# seg7_minishield.net
KiCad netlist of a schematic drawn in EAGLE
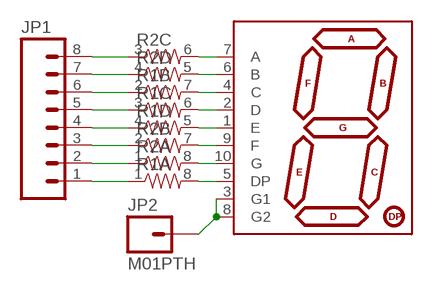
[diagram p0: schematic, sheet 1]

(export (version "E")
  (design (tool "Eeschema 10.0.6"))
  (components
    (comp (ref "JP1")
      (value "M081X08")
      (footprint "eagle-import:1X08")
      (libsource (lib "eagle-import") (part "M081X08"))
    )
    (comp (ref "JP2")
      (value "M01PTH")
      (footprint "eagle-import:1X01")
      (libsource (lib "eagle-import") (part "M01PTH"))
    )
    (comp (ref "R1")
      (value "RESISTOR-ARRAY0603-ARV")
      (footprint "eagle-import:0603-ARV")
      (libsource (lib "eagle-import") (part "RESISTOR-ARRAY0603-ARV"))
    )
    (comp (ref "R2")
      (value "RESISTOR-ARRAY0603-ARV")
      (footprint "eagle-import:0603-ARV")
      (libsource (lib "eagle-import") (part "RESISTOR-ARRAY0603-ARV"))
    )
    (comp (ref "U$1")
      (value "7-SEGMENT-DISPLAYPTH")
      (footprint "eagle-import:7-SEGMENT-DISPLAY")
      (libsource (lib "eagle-import") (part "7-SEGMENT-DISPLAYPTH"))
    )
  )
  (nets
    (net (code "1") (name "Net-(JP1-Pad1)") (class "Default")
      (node (ref "JP1") (pin "1") (pinfunction "1_1") (pintype "passive"))
      (node (ref "R1") (pin "1") (pinfunction "1_1") (pintype "passive"))
    )
    (net (code "2") (name "Net-(JP1-Pad2)") (class "Default")
      (node (ref "JP1") (pin "2") (pinfunction "2_2") (pintype "passive"))
      (node (ref "R2") (pin "1") (pinfunction "1_1") (pintype "passive"))
    )
    (net (code "3") (name "Net-(R1A-2)") (class "Default")
      (node (ref "R1") (pin "8") (pinfunction "2_8") (pintype "passive"))
      (node (ref "U$1") (pin "5") (pinfunction "DP_5") (pintype "bidirectional"))
    )
    (net (code "4") (name "Net-(R1B-1)") (class "Default")
      (node (ref "JP1") (pin "6") (pinfunction "6_6") (pintype "passive"))
      (node (ref "R1") (pin "2") (pinfunction "1_2") (pintype "passive"))
    )
    (net (code "5") (name "Net-(R1B-2)") (class "Default")
      (node (ref "R1") (pin "7") (pinfunction "2_7") (pintype "passive"))
      (node (ref "U$1") (pin "4") (pinfunction "C_4") (pintype "bidirectional"))
    )
    (net (code "6") (name "Net-(R1C-1)") (class "Default")
      (node (ref "JP1") (pin "5") (pinfunction "5_5") (pintype "passive"))
      (node (ref "R1") (pin "3") (pinfunction "1_3") (pintype "passive"))
    )
    (net (code "7") (name "Net-(R1C-2)") (class "Default")
      (node (ref "R1") (pin "6") (pinfunction "2_6") (pintype "passive"))
      (node (ref "U$1") (pin "2") (pinfunction "D_2") (pintype "bidirectional"))
    )
    (net (code "8") (name "Net-(R1D-1)") (class "Default")
      (node (ref "JP1") (pin "4") (pinfunction "4_4") (pintype "passive"))
      (node (ref "R1") (pin "4") (pinfunction "1_4") (pintype "passive"))
    )
    (net (code "9") (name "Net-(R1D-2)") (class "Default")
      (node (ref "R1") (pin "5") (pinfunction "2_5") (pintype "passive"))
      (node (ref "U$1") (pin "1") (pinfunction "E_1") (pintype "bidirectional"))
    )
    (net (code "10") (name "Net-(R2A-2)") (class "Default")
      (node (ref "R2") (pin "8") (pinfunction "2_8") (pintype "passive"))
      (node (ref "U$1") (pin "10") (pinfunction "G_10") (pintype "bidirectional"))
    )
    (net (code "11") (name "Net-(R2B-1)") (class "Default")
      (node (ref "JP1") (pin "3") (pinfunction "3_3") (pintype "passive"))
      (node (ref "R2") (pin "2") (pinfunction "1_2") (pintype "passive"))
    )
    (net (code "12") (name "Net-(R2B-2)") (class "Default")
      (node (ref "R2") (pin "7") (pinfunction "2_7") (pintype "passive"))
      (node (ref "U$1") (pin "9") (pinfunction "F_9") (pintype "bidirectional"))
    )
    (net (code "13") (name "Net-(R2C-1)") (class "Default")
      (node (ref "JP1") (pin "8") (pinfunction "8_8") (pintype "passive"))
      (node (ref "R2") (pin "3") (pinfunction "1_3") (pintype "passive"))
    )
    (net (code "14") (name "Net-(R2C-2)") (class "Default")
      (node (ref "R2") (pin "6") (pinfunction "2_6") (pintype "passive"))
      (node (ref "U$1") (pin "7") (pinfunction "A_7") (pintype "bidirectional"))
    )
    (net (code "15") (name "Net-(R2D-1)") (class "Default")
      (node (ref "JP1") (pin "7") (pinfunction "7_7") (pintype "passive"))
      (node (ref "R2") (pin "4") (pinfunction "1_4") (pintype "passive"))
    )
    (net (code "16") (name "Net-(R2D-2)") (class "Default")
      (node (ref "R2") (pin "5") (pinfunction "2_5") (pintype "passive"))
      (node (ref "U$1") (pin "6") (pinfunction "B_6") (pintype "bidirectional"))
    )
    (net (code "17") (name "Net-(U$1-G1)") (class "Default")
      (node (ref "JP2") (pin "1") (pinfunction "1_1") (pintype "passive"))
      (node (ref "U$1") (pin "3") (pinfunction "G1_3") (pintype "bidirectional"))
      (node (ref "U$1") (pin "8") (pinfunction "G2_8") (pintype "bidirectional"))
    )
  )
)
